# Power.net
KiCad netlist of a schematic drawn in Altium Designer
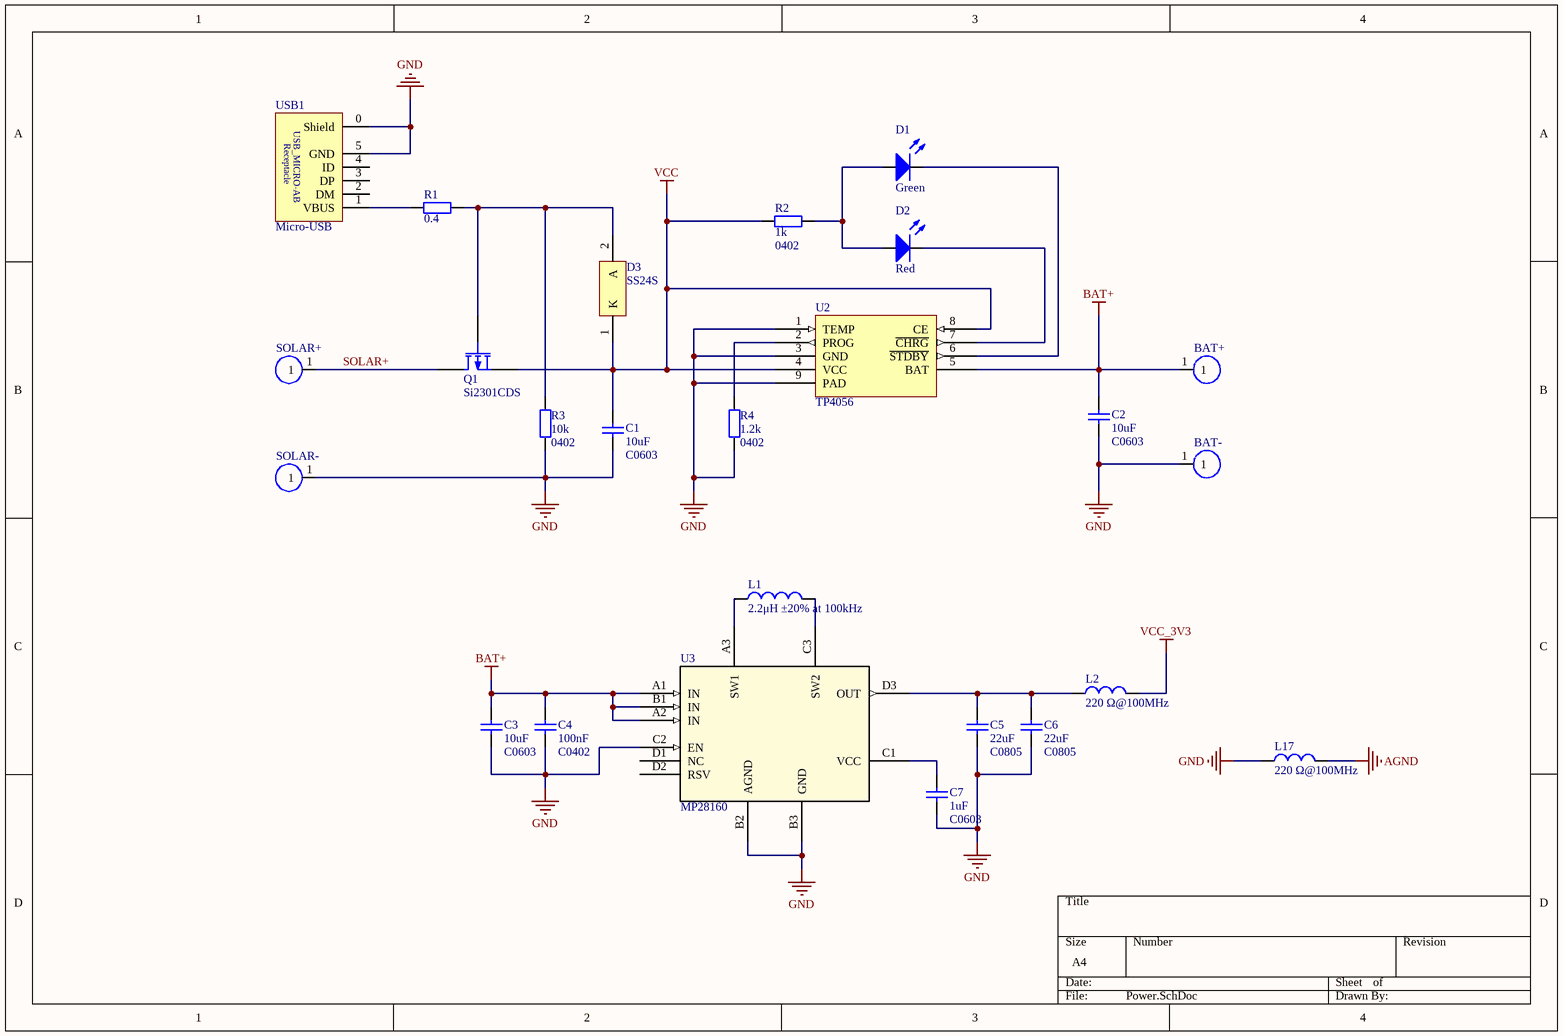
[diagram p0: Power.SchDoc]

(export (version "E")
  (design (tool "Eeschema 10.0.6"))
  (components
    (comp (ref "BAT+")
      (value "BAT+")
      (footprint "surface_pad")
      (description "PAD")
      (libsource (lib "RFID_CC1101PA2") (part "SURFACE_PAD"))
    )
    (comp (ref "BAT-")
      (value "BAT-")
      (footprint "surface_pad")
      (description "PAD")
      (libsource (lib "RFID_CC1101PA2") (part "SURFACE_PAD"))
    )
    (comp (ref "C1")
      (value "10uF")
      (footprint "1608[0603]")
      (description "Capacitor (0603,X5R,10uF,DC 10V,±10%) TDK")
      (fields (field (name "PACKAGEREFERENCE") "C0603") (field (name "PUBLISHER") "Altium Limited"))
      (libsource (lib "RFID_CC1101PA2") (part "C1608X5R1A106K080AC"))
    )
    (comp (ref "C2")
      (value "10uF")
      (footprint "1608[0603]")
      (description "Capacitor (0603,X5R,10uF,DC 10V,±10%) TDK")
      (fields (field (name "PACKAGEREFERENCE") "C0603") (field (name "PUBLISHER") "Altium Limited"))
      (libsource (lib "RFID_CC1101PA2") (part "C1608X5R1A106K080AC"))
    )
    (comp (ref "C3")
      (value "10uF")
      (footprint "1608[0603]")
      (description "Capacitor (0603,X5R,10uF,DC 10V,±10%) TDK")
      (fields (field (name "PACKAGEREFERENCE") "C0603") (field (name "PUBLISHER") "Altium Limited"))
      (libsource (lib "RFID_CC1101PA2") (part "C1608X5R1A106K080AC"))
    )
    (comp (ref "C4")
      (value "100nF")
      (footprint "0402")
      (description "Capacitor (0402,X5R,100nF,DC 10V,±10%) TDK")
      (fields (field (name "PACKAGEREFERENCE") "C0402") (field (name "PUBLISHER") "Altium Limited"))
      (libsource (lib "RFID_CC1101PA2") (part "CGA2B2X5R1A104K050BA"))
    )
    (comp (ref "C5")
      (value "22uF")
      (footprint "C0805")
      (description "Capacitor (0805,X5R,22uF,DC 10V,±10%) TDK")
      (fields (field (name "PACKAGEREFERENCE") "C0805") (field (name "PUBLISHER") "Altium Limited"))
      (libsource (lib "RFID_CC1101PA2") (part "C2012X5R1A226K125AB"))
    )
    (comp (ref "C6")
      (value "22uF")
      (footprint "C0805")
      (description "Capacitor (0805,X5R,22uF,DC 10V,±10%) TDK")
      (fields (field (name "PACKAGEREFERENCE") "C0805") (field (name "PUBLISHER") "Altium Limited"))
      (libsource (lib "RFID_CC1101PA2") (part "C2012X5R1A226K125AB"))
    )
    (comp (ref "C7")
      (value "1uF")
      (footprint "1608[0603]")
      (description "Capacitor (0603,X5R,1uF,DC 10V,+/-10%) TDK")
      (fields (field (name "PACKAGEREFERENCE") "C0603") (field (name "PUBLISHER") "Altium Limited"))
      (libsource (lib "RFID_CC1101PA2") (part "CGA3E2X5R1A105K080AA"))
    )
    (comp (ref "D1")
      (value "Green")
      (footprint "0603/K")
      (description "Standard 0603 SMD LED, Green, 2.1V,-40 °C to +100 °C")
      (fields (field (name "PUBLISHER") "Altium Limited"))
      (libsource (lib "RFID_CC1101PA2") (part "TLMG1100-GS08"))
    )
    (comp (ref "D2")
      (value "Red")
      (footprint "0603/K")
      (description "Standard 0603 SMD LED, Red, 2.1V,-40 °C to +100 °C")
      (fields (field (name "PUBLISHER") "Altium Limited"))
      (libsource (lib "RFID_CC1101PA2") (part "TLMS1100-GS08"))
    )
    (comp (ref "D3")
      (value "SS24S")
      (footprint "ONSC-SMA-2-403D-02_V")
      (description "Schottky Power Rectifier, 2-Pin SMA, VRRM=40V , VF=0.517V at IF=2.0A , Pb-Free, Tape and Reel")
      (fields (field (name "MANUFACTURER") "On Semiconductor"))
      (libsource (lib "RFID_CC1101PA2") (part "SS24S"))
    )
    (comp (ref "L1")
      (value "2.2μH ±20% at 100kHz")
      (footprint "INDP3230X10N")
      (description "inductor_commercial_power, 2.2μH ±20% at 100kHz, 2.6A, 3.2mm*3.0mm, -40～125°C")
      (libsource (lib "RFID_CC1101PA2") (part "SPM3010T-2R2M-LR"))
    )
    (comp (ref "L2")
      (value "220 Ω@100MHz")
      (footprint "RESC2012X07N")
      (description "220Ω, 2 A, 0805/2012 (EIA/JIS)")
      (libsource (lib "RFID_CC1101_869MHz") (part "FBMH2012HM221-T"))
    )
    (comp (ref "L17")
      (value "220 Ω@100MHz")
      (footprint "RESC2012X07N")
      (description "220Ω, 2 A, 0805/2012 (EIA/JIS)")
      (libsource (lib "RFID_CC1101_869MHz") (part "FBMH2012HM221-T"))
    )
    (comp (ref "Q1")
      (value "Si2301CDS")
      (footprint "SOT95P237X112-3N")
      (description "P-Channel MOSFET,VDS=-20V,VGS=8V,ID=3.1A,VGS(th)Min=0.4V,SOT-23")
      (fields (field (name "PUBLISHER") "Altium Limited"))
      (libsource (lib "RFID_CC1101PA2") (part "Si2301CDS"))
    )
    (comp (ref "R1")
      (value "0.4")
      (footprint "RESC3216X07N")
      (description "Resistor 1206(3216) 0.4Ω ±1% 1W AUTOMOTIVE GRADEPE_L series")
      (libsource (lib "RFID_CC1101PA2") (part "PE1206FRF470R4L"))
    )
    (comp (ref "R2")
      (value "1k")
      (footprint "RESC1005X04N")
      (description "Resistor 0402(1005) 1kΩ ±1%")
      (fields (field (name "PACKAGEREFERENCE") "0402"))
      (libsource (lib "RFID_CC1101PA2") (part "RC0402FR-071KL"))
    )
    (comp (ref "R3")
      (value "10k")
      (footprint "RESC1005X04N")
      (description "Resistor 0402(1005) 10kΩ ±1%")
      (fields (field (name "PACKAGEREFERENCE") "0402"))
      (libsource (lib "RFID_CC1101PA2") (part "RC0402FR-0710KL"))
    )
    (comp (ref "R4")
      (value "1.2k")
      (footprint "RESC1005X04N")
      (description "Resistor 0402(1005) 1.2kΩ ±1%")
      (fields (field (name "PACKAGEREFERENCE") "0402"))
      (libsource (lib "RFID_CC1101PA2") (part "RC0402FR-071K2L"))
    )
    (comp (ref "SOLAR+")
      (value "SOLAR+")
      (footprint "surface_pad")
      (description "PAD")
      (libsource (lib "RFID_CC1101PA2") (part "SURFACE_PAD"))
    )
    (comp (ref "SOLAR-")
      (value "SOLAR-")
      (footprint "surface_pad")
      (description "PAD")
      (libsource (lib "RFID_CC1101PA2") (part "SURFACE_PAD"))
    )
    (comp (ref "U2")
      (value "TP4056")
      (footprint "ESOP-9N")
      (description "1A线性锂离子电池充电器")
      (libsource (lib "BC26_GNSS") (part "TP4056"))
    )
    (comp (ref "U3")
      (value "MP28160")
      (footprint "CSP-12")
      (fields (field (name "MANUFACTURER_PART_NUMBER") "CSP-12"))
      (libsource (lib "RFID_CC1101PA2") (part "MP28160"))
    )
    (comp (ref "USB1")
      (value "Micro-USB")
      (footprint "USB_Micro_5P4J")
      (description "Receptacle,Micro 5脚贴片 不带定位柱")
      (libsource (lib "RFID_CC1101_869MHz") (part "USB/Micro-AB"))
    )
  )
  (nets
    (net (code "1") (name "/SOLAR+") (class "Default")
      (node (ref "Q1") (pin "3") (pinfunction "D_3") (pintype "passive"))
      (node (ref "SOLAR+") (pin "1") (pinfunction "1_1") (pintype "passive"))
    )
    (net (code "2") (name "AGND") (class "Default")
      (node (ref "L17") (pin "2") (pinfunction "2_2") (pintype "passive"))
    )
    (net (code "3") (name "BAT+") (class "Default")
      (node (ref "BAT+") (pin "1") (pinfunction "1_1") (pintype "passive"))
      (node (ref "C2") (pin "2") (pinfunction "2_2") (pintype "passive"))
      (node (ref "C3") (pin "2") (pinfunction "2_2") (pintype "passive"))
      (node (ref "C4") (pin "2") (pinfunction "2_2") (pintype "passive"))
      (node (ref "U2") (pin "5") (pinfunction "BAT_5") (pintype "power_in"))
      (node (ref "U3") (pin "A1") (pinfunction "IN_A1") (pintype "input"))
      (node (ref "U3") (pin "A2") (pinfunction "IN_A2") (pintype "input"))
      (node (ref "U3") (pin "B1") (pinfunction "IN_B1") (pintype "input"))
    )
    (net (code "4") (name "GND") (class "Default")
      (node (ref "BAT-") (pin "1") (pinfunction "1_1") (pintype "passive"))
      (node (ref "C1") (pin "1") (pinfunction "1_1") (pintype "passive"))
      (node (ref "C2") (pin "1") (pinfunction "1_1") (pintype "passive"))
      (node (ref "C3") (pin "1") (pinfunction "1_1") (pintype "passive"))
      (node (ref "C4") (pin "1") (pinfunction "1_1") (pintype "passive"))
      (node (ref "C5") (pin "1") (pinfunction "1_1") (pintype "passive"))
      (node (ref "C6") (pin "1") (pinfunction "1_1") (pintype "passive"))
      (node (ref "C7") (pin "1") (pinfunction "1_1") (pintype "passive"))
      (node (ref "L17") (pin "1") (pinfunction "1_1") (pintype "passive"))
      (node (ref "R3") (pin "1") (pinfunction "1_1") (pintype "passive"))
      (node (ref "R4") (pin "1") (pinfunction "1_1") (pintype "passive"))
      (node (ref "SOLAR-") (pin "1") (pinfunction "1_1") (pintype "passive"))
      (node (ref "U2") (pin "1") (pinfunction "TEMP_1") (pintype "input"))
      (node (ref "U2") (pin "3") (pinfunction "GND_3") (pintype "power_in"))
      (node (ref "U2") (pin "9") (pinfunction "PAD_9") (pintype "passive"))
      (node (ref "U3") (pin "B2") (pinfunction "AGND_B2") (pintype "power_in"))
      (node (ref "U3") (pin "B3") (pinfunction "GND_B3") (pintype "power_in"))
      (node (ref "U3") (pin "C2") (pinfunction "EN_C2") (pintype "input"))
      (node (ref "USB1") (pin "0") (pinfunction "Shield_0") (pintype "passive"))
      (node (ref "USB1") (pin "5") (pinfunction "GND_5") (pintype "passive"))
    )
    (net (code "5") (name "Net-(D1-PadA)") (class "Default")
      (node (ref "D1") (pin "A") (pinfunction "A_A") (pintype "passive"))
      (node (ref "D2") (pin "A") (pinfunction "A_A") (pintype "passive"))
      (node (ref "R2") (pin "2") (pinfunction "2_2") (pintype "passive"))
    )
    (net (code "6") (name "Net-(D3-A)") (class "Default")
      (node (ref "D3") (pin "2") (pinfunction "A_2") (pintype "passive"))
      (node (ref "Q1") (pin "1") (pinfunction "G_1") (pintype "passive"))
      (node (ref "R1") (pin "2") (pinfunction "2_2") (pintype "passive"))
      (node (ref "R3") (pin "2") (pinfunction "2_2") (pintype "passive"))
    )
    (net (code "7") (name "Net-(U2-PROG)") (class "Default")
      (node (ref "R4") (pin "2") (pinfunction "2_2") (pintype "passive"))
      (node (ref "U2") (pin "2") (pinfunction "PROG_2") (pintype "output"))
    )
    (net (code "8") (name "Net-(U2-~{CHRG})") (class "Default")
      (node (ref "D2") (pin "K") (pinfunction "K_K") (pintype "passive"))
      (node (ref "U2") (pin "7") (pinfunction "~{CHRG}_7") (pintype "output"))
    )
    (net (code "9") (name "Net-(U2-~{STDBY})") (class "Default")
      (node (ref "D1") (pin "K") (pinfunction "K_K") (pintype "passive"))
      (node (ref "U2") (pin "6") (pinfunction "~{STDBY}_6") (pintype "output"))
    )
    (net (code "10") (name "Net-(U3-OUT)") (class "Default")
      (node (ref "C5") (pin "2") (pinfunction "2_2") (pintype "passive"))
      (node (ref "C6") (pin "2") (pinfunction "2_2") (pintype "passive"))
      (node (ref "L2") (pin "1") (pinfunction "1_1") (pintype "passive"))
      (node (ref "U3") (pin "D3") (pinfunction "OUT_D3") (pintype "output"))
    )
    (net (code "11") (name "Net-(U3-SW1)") (class "Default")
      (node (ref "L1") (pin "1") (pinfunction "1_1") (pintype "passive"))
      (node (ref "U3") (pin "A3") (pinfunction "SW1_A3") (pintype "passive"))
    )
    (net (code "12") (name "Net-(U3-SW2)") (class "Default")
      (node (ref "L1") (pin "2") (pinfunction "2_2") (pintype "passive"))
      (node (ref "U3") (pin "C3") (pinfunction "SW2_C3") (pintype "passive"))
    )
    (net (code "13") (name "Net-(U3-VCC)") (class "Default")
      (node (ref "C7") (pin "2") (pinfunction "2_2") (pintype "passive"))
      (node (ref "U3") (pin "C1") (pinfunction "VCC_C1") (pintype "power_in"))
    )
    (net (code "14") (name "Net-(USB1-VBUS)") (class "Default")
      (node (ref "R1") (pin "1") (pinfunction "1_1") (pintype "passive"))
      (node (ref "USB1") (pin "1") (pinfunction "VBUS_1") (pintype "passive"))
    )
    (net (code "15") (name "VCC") (class "Default")
      (node (ref "C1") (pin "2") (pinfunction "2_2") (pintype "passive"))
      (node (ref "D3") (pin "1") (pinfunction "K_1") (pintype "passive"))
      (node (ref "Q1") (pin "2") (pinfunction "S_2") (pintype "passive"))
      (node (ref "R2") (pin "1") (pinfunction "1_1") (pintype "passive"))
      (node (ref "U2") (pin "4") (pinfunction "VCC_4") (pintype "power_in"))
      (node (ref "U2") (pin "8") (pinfunction "CE_8") (pintype "input"))
    )
    (net (code "16") (name "VCC_3V3") (class "Default")
      (node (ref "L2") (pin "2") (pinfunction "2_2") (pintype "passive"))
    )
    (net (code "17") (name "unconnected-(U3-NC-PadD1)") (class "Default")
      (node (ref "U3") (pin "D1") (pinfunction "NC_D1") (pintype "passive"))
    )
    (net (code "18") (name "unconnected-(U3-RSV-PadD2)") (class "Default")
      (node (ref "U3") (pin "D2") (pinfunction "RSV_D2") (pintype "passive"))
    )
    (net (code "19") (name "unconnected-(USB1-DM-Pad2)") (class "Default")
      (node (ref "USB1") (pin "2") (pinfunction "DM_2") (pintype "passive"))
    )
    (net (code "20") (name "unconnected-(USB1-DP-Pad3)") (class "Default")
      (node (ref "USB1") (pin "3") (pinfunction "DP_3") (pintype "passive"))
    )
    (net (code "21") (name "unconnected-(USB1-ID-Pad4)") (class "Default")
      (node (ref "USB1") (pin "4") (pinfunction "ID_4") (pintype "passive"))
    )
  )
)
